# Power_Converter_5V_as_TO-3_replacement.net
KiCad netlist of a schematic drawn in Altium Designer
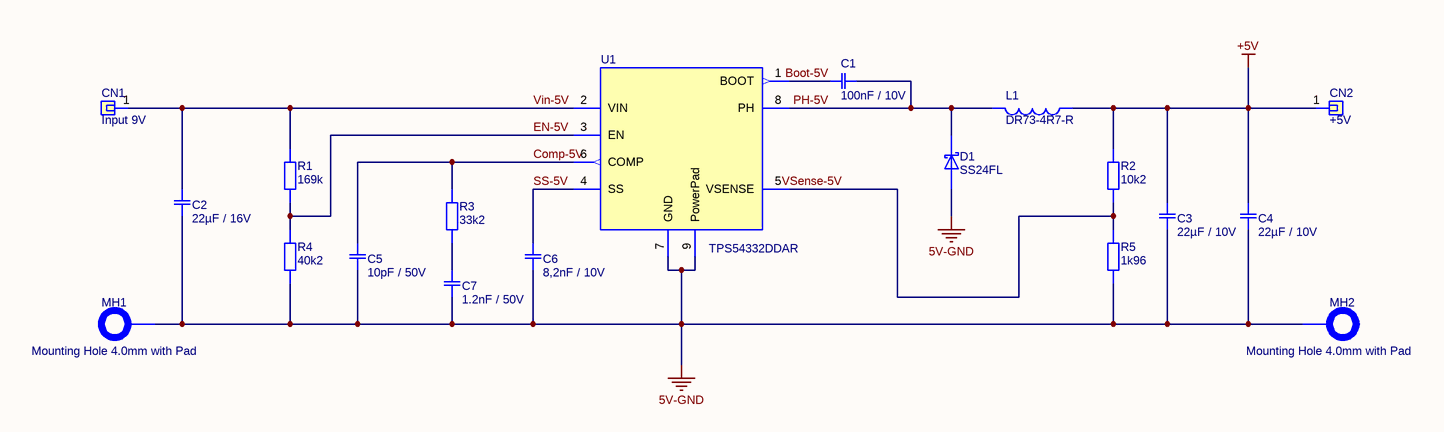
[diagram p0: Power Converter 5V as TO-3 replacement.SchDoc]

(export (version "E")
  (design (tool "Eeschema 10.0.6"))
  (components
    (comp (ref "C1")
      (value "100nF / 10V")
      (footprint "CAP CER SMD 0402 100nF 10V Murata GRM155R71A104KA01D")
      (description "CAP CER 0.1UF 10V X7R 0402")
      (fields (field (name "VOLTAGE") "10V") (field (name "TOLERANCE") "10%"))
      (libsource (lib "PCB-Tech Cloud") (part "Capacitor"))
    )
    (comp (ref "C2")
      (value "22µF / 16V")
      (footprint "CAP CER SMD 1210 22µF 16V Murata GRM32ER61C226ME20L")
      (description "Ceramic capacitor SMD 1210 22 µF 16 V 20 %")
      (fields (field (name "TOLERANCE") "20%") (field (name "VOLTAGE") "16V"))
      (libsource (lib "PCB-Tech Cloud") (part "Capacitor"))
    )
    (comp (ref "C3")
      (value "22µF / 10V")
      (footprint "CAP CER SMD 0805 22µF 10V Murata GRM21BR61A226ME44L")
      (description "Multilayer Ceramic Capacitors MLCC - SMD/SMT 0805 22uF 10volts X5R 20%")
      (fields (field (name "VOLTAGE") "10V") (field (name "TOLERANCE") "20%"))
      (libsource (lib "PCB-Tech Cloud") (part "Capacitor"))
    )
    (comp (ref "C4")
      (value "22µF / 10V")
      (footprint "CAP CER SMD 0805 22µF 10V Murata GRM21BR61A226ME44L")
      (description "Multilayer Ceramic Capacitors MLCC - SMD/SMT 0805 22uF 10volts X5R 20%")
      (fields (field (name "VOLTAGE") "10V") (field (name "TOLERANCE") "20%"))
      (libsource (lib "PCB-Tech Cloud") (part "Capacitor"))
    )
    (comp (ref "C5")
      (value "10pF / 50V")
      (footprint "CAP CER SMD 0805 10pF 50V Samsung CL21C100JBANNNC")
      (description "Cap Ceramic 10pF 50VDC C0G 5% SMD 0805 Paper T/R")
      (fields (field (name "TOLERANCE") "5%"))
      (libsource (lib "PCB-Tech Cloud") (part "Capacitor"))
    )
    (comp (ref "C6")
      (value "8,2nF / 10V")
      (footprint "CAP CER SMD 0201 8,2nF 10V Murata GRM033R71A822KA01D")
      (description "Multilayer Ceramic Capacitors MLCC - SMD/SMT 0.0082uF 10volts 10%")
      (fields (field (name "TOLERANCE") "10%"))
      (libsource (lib "PCB-Tech Cloud") (part "Capacitor"))
    )
    (comp (ref "C7")
      (value "1.2nF / 50V")
      (footprint "CAP CER SMD 0805 1.2nF 50V Samsung CL21C122JBFNNNE")
      (description "Ceramic capacitor SMD-0805 1.2nF /50V NP0# J +-5% SAMSUNG , RoHS")
      (fields (field (name "TOLERANCE") "5%"))
      (libsource (lib "PCB-Tech Cloud") (part "Capacitor"))
    )
    (comp (ref "CN1")
      (value "Input 9V")
      (footprint "Printed Circuit Pin 1.02mm 3125-2-00-80-00-00-08-0")
      (description "CONN PC PIN CIRC 0.040DIA TIN")
      (libsource (lib "") (part "CONN 01x01_1"))
    )
    (comp (ref "CN2")
      (value "+5V")
      (footprint "Printed Circuit Pin 1.02mm 3125-2-00-80-00-00-08-0")
      (description "CONN PC PIN CIRC 0.040DIA TIN")
      (libsource (lib "PCB-Tech Cloud") (part "CONN 01x01"))
    )
    (comp (ref "D1")
      (value "SS24FL")
      (footprint "SS24FL")
      (description "40V, 2A SCHOTTKY IN SOD123F")
      (libsource (lib "PCB-Tech Cloud") (part "Schottky Diode"))
    )
    (comp (ref "L1")
      (value "DR73-4R7-R")
      (footprint "Inductor SMD 4.7µH Eatont DR73-4R7-R")
      (description "Ind Power Shielded Wirewound 4.7uH 20% 100KHz Ferrite 3.09A T/R")
      (fields (field (name "TOLERANCE") "20%"))
      (libsource (lib "PCB-Tech Cloud") (part "Inductor Standard"))
    )
    (comp (ref "MH1")
      (value "Mounting Hole 4.0mm with Pad")
      (footprint "Mounting Hole 4mm with Pad")
      (libsource (lib "PCB-Tech Cloud") (part "Mounting Hole with Pad"))
    )
    (comp (ref "MH2")
      (value "Mounting Hole 4.0mm with Pad")
      (footprint "Mounting Hole 4mm with Pad")
      (libsource (lib "PCB-Tech Cloud") (part "Mounting Hole with Pad"))
    )
    (comp (ref "R1")
      (value "169k")
      (footprint "RES SMD 0402 169k Vishay CRCW0402169KFKED")
      (description "VISHAY - CRCW0402169KFKED - RES, THICK FILM, 169K, 1%, 0.063W, 0402, REEL")
      (fields (field (name "TOLERANCE") "1%"))
      (libsource (lib "PCB-Tech Cloud") (part "Resistor"))
    )
    (comp (ref "R2")
      (value "10k2")
      (footprint "RES SMD 0402 10k2 Vishay CRCW040210K2FKED")
      (fields (field (name "TOLERANCE") "1%"))
      (libsource (lib "PCB-Tech Cloud") (part "Resistor"))
    )
    (comp (ref "R3")
      (value "33k2")
      (footprint "RES SMD 0402 33k2 Vishay CRCW040233K2FKED")
      (description "Res Thick Film 0402 33.2K Ohm 1% 1/16W 100ppm/C Molded SMD Paper T/R")
      (fields (field (name "TOLERANCE") "1%"))
      (libsource (lib "PCB-Tech Cloud") (part "Resistor"))
    )
    (comp (ref "R4")
      (value "40k2")
      (footprint "RES SMD 0402 40k2 Vishay CRCW040240K2FKED")
      (description "Res Thick Film 0402 40.2K Ohm 1% 1/16W 100ppm/C Molded SMD SMD Paper T/R")
      (fields (field (name "TOLERANCE") "1%"))
      (libsource (lib "PCB-Tech Cloud") (part "Resistor"))
    )
    (comp (ref "R5")
      (value "1k96")
      (footprint "RES SMD 0402 1k96 Vishay CRCW04021K96FKED")
      (description "VISHAY         CRCW04021K96FKED             RES, THICK FILM, 1K96, 1%, 0.063W, 0402")
      (fields (field (name "TOLERANCE") "1%"))
      (libsource (lib "PCB-Tech Cloud") (part "Resistor"))
    )
    (comp (ref "U1")
      (value "TPS54332DDAR")
      (footprint "DC-DC Converter (Buck) TPS54332DDAR SO-Power Pad")
      (description "TEXAS INSTRUMENTS - TPS54332DDAR - DC/DC CONV, BUCK, 1MHZ, SOIC-8")
      (libsource (lib "PCB-Tech Cloud") (part "DC-DC Converter (Buck) TPS54332DDAR SO-Power Pad"))
    )
  )
  (nets
    (net (code "1") (name "+5V") (class "Default")
      (node (ref "C3") (pin "2") (pinfunction "2_2") (pintype "passive"))
      (node (ref "C4") (pin "2") (pinfunction "2_2") (pintype "passive"))
      (node (ref "CN2") (pin "1") (pinfunction "1_1") (pintype "passive"))
      (node (ref "L1") (pin "2") (pinfunction "2_2") (pintype "passive"))
      (node (ref "R2") (pin "2") (pinfunction "2_2") (pintype "passive"))
    )
    (net (code "2") (name "/Boot-5V") (class "Default")
      (node (ref "C1") (pin "1") (pinfunction "1_1") (pintype "passive"))
      (node (ref "U1") (pin "1") (pinfunction "BOOT_1") (pintype "output"))
    )
    (net (code "3") (name "/Comp-5V") (class "Default")
      (node (ref "C5") (pin "2") (pinfunction "2_2") (pintype "passive"))
      (node (ref "R3") (pin "2") (pinfunction "2_2") (pintype "passive"))
      (node (ref "U1") (pin "6") (pinfunction "COMP_6") (pintype "output"))
    )
    (net (code "4") (name "/EN-5V") (class "Default")
      (node (ref "R1") (pin "1") (pinfunction "1_1") (pintype "passive"))
      (node (ref "R4") (pin "2") (pinfunction "2_2") (pintype "passive"))
      (node (ref "U1") (pin "3") (pinfunction "EN_3") (pintype "passive"))
    )
    (net (code "5") (name "/PH-5V") (class "Default")
      (node (ref "C1") (pin "2") (pinfunction "2_2") (pintype "passive"))
      (node (ref "D1") (pin "1") (pinfunction "1_1") (pintype "passive"))
      (node (ref "L1") (pin "1") (pinfunction "1_1") (pintype "passive"))
      (node (ref "U1") (pin "8") (pinfunction "PH_8") (pintype "power_in"))
    )
    (net (code "6") (name "/SS-5V") (class "Default")
      (node (ref "C6") (pin "2") (pinfunction "2_2") (pintype "passive"))
      (node (ref "U1") (pin "4") (pinfunction "SS_4") (pintype "passive"))
    )
    (net (code "7") (name "/VSense-5V") (class "Default")
      (node (ref "R2") (pin "1") (pinfunction "1_1") (pintype "passive"))
      (node (ref "R5") (pin "2") (pinfunction "2_2") (pintype "passive"))
      (node (ref "U1") (pin "5") (pinfunction "VSENSE_5") (pintype "passive"))
    )
    (net (code "8") (name "/Vin-5V") (class "Default")
      (node (ref "C2") (pin "2") (pinfunction "2_2") (pintype "passive"))
      (node (ref "CN1") (pin "1") (pinfunction "1_1") (pintype "passive"))
      (node (ref "R1") (pin "2") (pinfunction "2_2") (pintype "passive"))
      (node (ref "U1") (pin "2") (pinfunction "VIN_2") (pintype "power_in"))
    )
    (net (code "9") (name "5V-GND") (class "Default")
      (node (ref "C2") (pin "1") (pinfunction "1_1") (pintype "passive"))
      (node (ref "C3") (pin "1") (pinfunction "1_1") (pintype "passive"))
      (node (ref "C4") (pin "1") (pinfunction "1_1") (pintype "passive"))
      (node (ref "C5") (pin "1") (pinfunction "1_1") (pintype "passive"))
      (node (ref "C6") (pin "1") (pinfunction "1_1") (pintype "passive"))
      (node (ref "C7") (pin "1") (pinfunction "1_1") (pintype "passive"))
      (node (ref "D1") (pin "2") (pinfunction "2_2") (pintype "passive"))
      (node (ref "MH1") (pin "1") (pinfunction "1_1") (pintype "power_in"))
      (node (ref "MH2") (pin "1") (pinfunction "1_1") (pintype "power_in"))
      (node (ref "R4") (pin "1") (pinfunction "1_1") (pintype "passive"))
      (node (ref "R5") (pin "1") (pinfunction "1_1") (pintype "passive"))
      (node (ref "U1") (pin "7") (pinfunction "GND_7") (pintype "power_in"))
      (node (ref "U1") (pin "9") (pinfunction "PowerPad_9") (pintype "power_in"))
    )
    (net (code "10") (name "Net-(C7-Pad2)") (class "Default")
      (node (ref "C7") (pin "2") (pinfunction "2_2") (pintype "passive"))
      (node (ref "R3") (pin "1") (pinfunction "1_1") (pintype "passive"))
    )
  )
)
